# Test_Jig_PPM-Encoder.net
KiCad netlist of a schematic drawn in Altium Designer
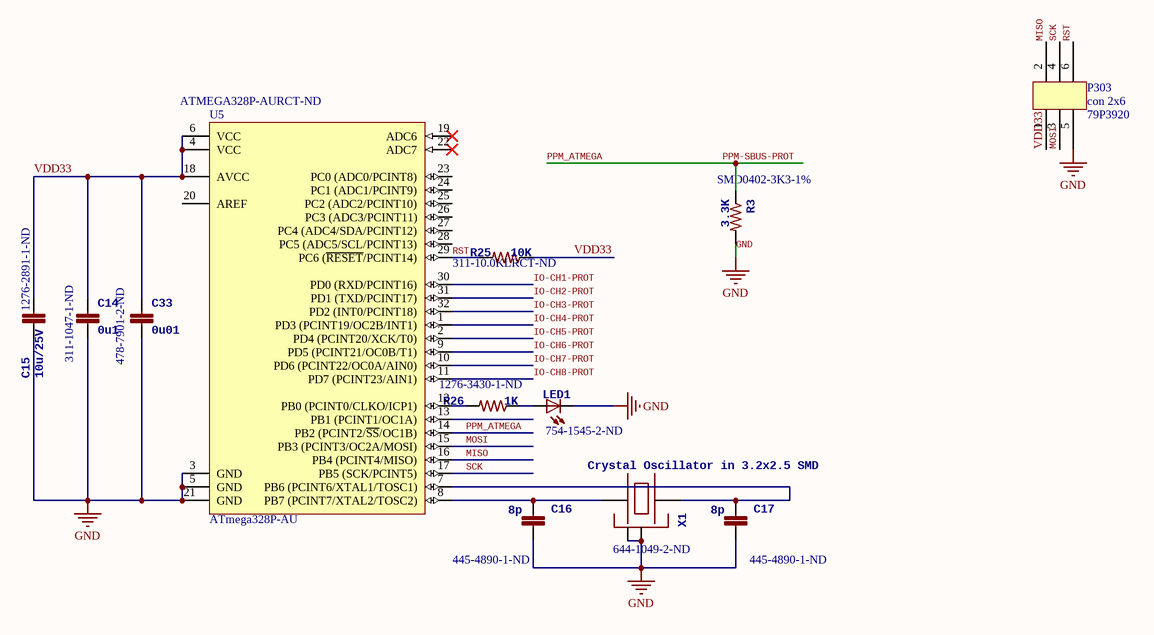
[diagram p0: Test_Jig_PPM-Encoder.SchDoc]

(export (version "E")
  (design (tool "Eeschema 10.0.6"))
  (components
    (comp (ref "C14")
      (value "0u1")
      (footprint "0402-CAP")
      (description "CAP CER 0.1UF 16V Y5V 0402")
      (fields
        (field (name "PARTNO") "CC0402ZRY5V7BB104")
        (field (name "SUPPLIER PART NUMBER 1") "311-1047-1-ND")
        (field (name "3DR_PARTNO") "ECM0700")
      )
      (libsource (lib "pixhawk2") (part "CAP0402"))
    )
    (comp (ref "C15")
      (value "10u/25V")
      (footprint "0805-CAP")
      (description "CAP CER 10UF 25V 10% X5R 0805")
      (fields
        (field (name "PARTNO") "CL21A106KAYNNNE")
        (field (name "SUPPLIER PART NUMBER 1") "1276-2891-1-ND")
        (field (name "3DR_PARTNO") "ECM0714")
      )
      (libsource (lib "pixhawk2") (part "CAP0805"))
    )
    (comp (ref "C16")
      (value "8p")
      (footprint "0402-CAP")
      (description "CAP CER 8PF 50V C0G 0402")
      (fields
        (field (name "PARTNO") "C1005C0G1H080C")
        (field (name "SUPPLIER PART NUMBER 1") "445-4890-1-ND")
        (field (name "3DR_PARTNO") "ECM0710")
      )
      (libsource (lib "") (part "CAP0402_1"))
    )
    (comp (ref "C17")
      (value "8p")
      (footprint "0402-CAP")
      (description "CAP CER 8PF 50V C0G 0402")
      (fields
        (field (name "PARTNO") "C1005C0G1H080C")
        (field (name "SUPPLIER PART NUMBER 1") "445-4890-1-ND")
        (field (name "3DR_PARTNO") "ECM0710")
      )
      (libsource (lib "") (part "CAP0402_1"))
    )
    (comp (ref "C33")
      (value "0u01")
      (footprint "0603-CAP")
      (description "CAP CER 10000PF 25V 5% X7R 0603")
      (fields
        (field (name "PARTNO") "06033C103JAT2A")
        (field (name "SUPPLIER PART NUMBER 1") "478-7901-2-ND")
        (field (name "3DR_PARTNO") "ECM0620")
      )
      (libsource (lib "pixhawk2") (part "CAP0603"))
    )
    (comp (ref "LED1")
      (value "LED0603_Green")
      (footprint "0603-LED-Blue")
      (description "LED GREEN ROUND CLEAR SMD")
      (fields
        (field (name "SUPPLIER PART NUMBER 1") "754-1545-2-ND")
        (field (name "3DR_PARTNO") "ECM0494")
        (field (name "PARTNO") "APTD1608CGCK")
      )
      (libsource (lib "pixhawk2") (part "LED0603_Blue"))
    )
    (comp (ref "P303")
      (value "con 2x6")
      (footprint "TSW-103-07-G-D")
      (description "Connector, Header, 6Pos, 2.54MM, Vert, THT, Au")
      (fields (field (name "SUPPLIER PART NUMBER 1") "79P3920") (field (name "3DR_PARTNO") "PRT0445"))
      (libsource (lib "PCA_0005_FULL_CB_REV_A") (part "con 2x6"))
    )
    (comp (ref "R3")
      (value "3.3K")
      (footprint "C0402")
      (fields (field (name "SUPPLIER PART NUMBER 1") "SMD0402-3K3-1%"))
      (libsource (lib "DIYdrones3") (part "RESISTOR0402"))
    )
    (comp (ref "R25")
      (value "10K")
      (footprint "0402-RES")
      (description "RES 10K OHM 1/16W 1% 0402 SMD")
      (fields
        (field (name "PARTNO") "RC0402FR-0710KL")
        (field (name "SUPPLIER PART NUMBER 1") "311-10.0KLRCT-ND")
        (field (name "3DR_PARTNO") "ECM0800")
      )
      (libsource (lib "pixhawk2") (part "RESISTOR0402-RES"))
    )
    (comp (ref "R26")
      (value "1K")
      (footprint "0402-RES")
      (description "RES 1K OHM 1/16W 1% 0402")
      (fields
        (field (name "PARTNO") "RC1005F102CS")
        (field (name "SUPPLIER PART NUMBER 1") "1276-3430-1-ND")
        (field (name "3DR_PARTNO") "ECM0804")
      )
      (libsource (lib "pixhawk2") (part "RESISTOR0402-RES"))
    )
    (comp (ref "U5")
      (value "ATmega328P-AU")
      (footprint "32A_N")
      (fields (field (name "SUPPLIER PART NUMBER 1") "ATMEGA328P-AURCT-ND"))
      (libsource (lib "Atmel Microcontroller megaAVR") (part "ATmega328P-AU"))
    )
    (comp (ref "X1")
      (value "Crystal Oscillator in 3.2x2.5 SMD")
      (footprint "OSCILLATOR-3.2X2.5")
      (description "CRYSTAL 16MHZ 8PF SMD")
      (fields
        (field (name "SUPPLIER PART NUMBER 1") "644-1049-2-ND")
        (field (name "PARTNO") "NX3225SA-16.000MHZ-STD-CSR-1")
      )
      (libsource (lib "pixhawk2") (part "OSCILLATOR-3.2X2.5"))
    )
  )
  (nets
    (net (code "1") (name "/IO-CH1-PROT") (class "Default")
      (node (ref "U5") (pin "30") (pinfunction "PD0_(RXD/PCINT16)_30") (pintype "bidirectional"))
    )
    (net (code "2") (name "/IO-CH2-PROT") (class "Default")
      (node (ref "U5") (pin "31") (pinfunction "PD1_(TXD/PCINT17)_31") (pintype "bidirectional"))
    )
    (net (code "3") (name "/IO-CH3-PROT") (class "Default")
      (node (ref "U5") (pin "32") (pinfunction "PD2_(INT0/PCINT18)_32") (pintype "bidirectional"))
    )
    (net (code "4") (name "/IO-CH4-PROT") (class "Default")
      (node (ref "U5") (pin "1") (pinfunction "PD3_(PCINT19/OC2B/INT1)_1") (pintype "bidirectional"))
    )
    (net (code "5") (name "/IO-CH5-PROT") (class "Default")
      (node (ref "U5") (pin "2") (pinfunction "PD4_(PCINT20/XCK/T0)_2") (pintype "bidirectional"))
    )
    (net (code "6") (name "/IO-CH6-PROT") (class "Default")
      (node (ref "U5") (pin "9") (pinfunction "PD5_(PCINT21/OC0B/T1)_9") (pintype "bidirectional"))
    )
    (net (code "7") (name "/IO-CH7-PROT") (class "Default")
      (node (ref "U5") (pin "10") (pinfunction "PD6_(PCINT22/OC0A/AIN0)_10") (pintype "bidirectional"))
    )
    (net (code "8") (name "/IO-CH8-PROT") (class "Default")
      (node (ref "U5") (pin "11") (pinfunction "PD7_(PCINT23/AIN1)_11") (pintype "bidirectional"))
    )
    (net (code "9") (name "/MISO") (class "Default")
      (node (ref "P303") (pin "2") (pinfunction "2_2") (pintype "passive"))
      (node (ref "U5") (pin "16") (pinfunction "PB4_(PCINT4/MISO)_16") (pintype "bidirectional"))
    )
    (net (code "10") (name "/MOSI") (class "Default")
      (node (ref "P303") (pin "3") (pinfunction "3_3") (pintype "passive"))
      (node (ref "U5") (pin "15") (pinfunction "PB3_(PCINT3/OC2A/MOSI)_15") (pintype "bidirectional"))
    )
    (net (code "11") (name "/PPM-SBUS-PROT") (class "Default")
      (node (ref "R3") (pin "1") (pinfunction "1_1") (pintype "passive"))
      (node (ref "U5") (pin "14") (pinfunction "PB2_(PCINT2/~{SS}/OC1B)_14") (pintype "bidirectional"))
    )
    (net (code "12") (name "/RST") (class "Default")
      (node (ref "P303") (pin "6") (pinfunction "6_6") (pintype "passive"))
      (node (ref "R25") (pin "P$2") (pinfunction "2_P$2") (pintype "passive"))
      (node (ref "U5") (pin "29") (pinfunction "PC6_(~{RESET}/PCINT14)_29") (pintype "bidirectional"))
    )
    (net (code "13") (name "/SCK") (class "Default")
      (node (ref "P303") (pin "4") (pinfunction "4_4") (pintype "passive"))
      (node (ref "U5") (pin "17") (pinfunction "PB5_(SCK/PCINT5)_17") (pintype "bidirectional"))
    )
    (net (code "14") (name "/VDD33") (class "Default")
      (node (ref "C14") (pin "P$1") (pinfunction "1_P$1") (pintype "passive"))
      (node (ref "C15") (pin "P$1") (pinfunction "1_P$1") (pintype "passive"))
      (node (ref "C33") (pin "P$1") (pinfunction "1_P$1") (pintype "passive"))
      (node (ref "P303") (pin "1") (pinfunction "1_1") (pintype "passive"))
      (node (ref "R25") (pin "P$1") (pinfunction "1_P$1") (pintype "passive"))
      (node (ref "U5") (pin "18") (pinfunction "AVCC_18") (pintype "power_in"))
      (node (ref "U5") (pin "4") (pinfunction "VCC_4") (pintype "power_in"))
      (node (ref "U5") (pin "6") (pinfunction "VCC_6") (pintype "power_in"))
    )
    (net (code "15") (name "GND") (class "Default")
      (node (ref "C14") (pin "P$2") (pinfunction "2_P$2") (pintype "passive"))
      (node (ref "C15") (pin "P$2") (pinfunction "2_P$2") (pintype "passive"))
      (node (ref "C16") (pin "P$1") (pinfunction "1_P$1") (pintype "passive"))
      (node (ref "C17") (pin "P$1") (pinfunction "1_P$1") (pintype "passive"))
      (node (ref "C33") (pin "P$2") (pinfunction "2_P$2") (pintype "passive"))
      (node (ref "LED1") (pin "C") (pinfunction "C_C") (pintype "passive"))
      (node (ref "P303") (pin "5") (pinfunction "5_5") (pintype "passive"))
      (node (ref "R3") (pin "2") (pinfunction "2_2") (pintype "passive"))
      (node (ref "U5") (pin "21") (pinfunction "GND_21") (pintype "power_in"))
      (node (ref "U5") (pin "3") (pinfunction "GND_3") (pintype "power_in"))
      (node (ref "U5") (pin "5") (pinfunction "GND_5") (pintype "power_in"))
      (node (ref "X1") (pin "2") (pinfunction "NC_2_2") (pintype "open_emitter"))
      (node (ref "X1") (pin "4") (pinfunction "NC_4_4") (pintype "open_emitter"))
    )
    (net (code "16") (name "Net-(C16-2)") (class "Default")
      (node (ref "C16") (pin "P$2") (pinfunction "2_P$2") (pintype "passive"))
      (node (ref "U5") (pin "8") (pinfunction "PB7_(PCINT7/XTAL2/TOSC2)_8") (pintype "bidirectional"))
      (node (ref "X1") (pin "1") (pinfunction "1_1") (pintype "passive"))
    )
    (net (code "17") (name "Net-(C17-2)") (class "Default")
      (node (ref "C17") (pin "P$2") (pinfunction "2_P$2") (pintype "passive"))
      (node (ref "U5") (pin "7") (pinfunction "PB6_(PCINT6/XTAL1/TOSC1)_7") (pintype "bidirectional"))
      (node (ref "X1") (pin "3") (pinfunction "3_3") (pintype "passive"))
    )
    (net (code "18") (name "Net-(R26-1)") (class "Default")
      (node (ref "LED1") (pin "A") (pinfunction "A_A") (pintype "passive"))
      (node (ref "R26") (pin "P$1") (pinfunction "1_P$1") (pintype "passive"))
    )
    (net (code "19") (name "Net-(R26-2)") (class "Default")
      (node (ref "R26") (pin "P$2") (pinfunction "2_P$2") (pintype "passive"))
      (node (ref "U5") (pin "12") (pinfunction "PB0_(PCINT0/CLKO/ICP1)_12") (pintype "bidirectional"))
    )
    (net (code "20") (name "unconnected-(U5-ADC6-Pad19)") (class "Default")
      (node (ref "U5") (pin "19") (pinfunction "ADC6_19") (pintype "input+no_connect"))
    )
    (net (code "21") (name "unconnected-(U5-ADC7-Pad22)") (class "Default")
      (node (ref "U5") (pin "22") (pinfunction "ADC7_22") (pintype "input+no_connect"))
    )
    (net (code "22") (name "unconnected-(U5-AREF-Pad20)") (class "Default")
      (node (ref "U5") (pin "20") (pinfunction "AREF_20") (pintype "passive"))
    )
    (net (code "23") (name "unconnected-(U5-PB1_(PCINT1{slash}OC1A)-Pad13)") (class "Default")
      (node (ref "U5") (pin "13") (pinfunction "PB1_(PCINT1/OC1A)_13") (pintype "bidirectional"))
    )
    (net (code "24") (name "unconnected-(U5-PC0_(ADC0{slash}PCINT8)-Pad23)") (class "Default")
      (node (ref "U5") (pin "23") (pinfunction "PC0_(ADC0/PCINT8)_23") (pintype "bidirectional"))
    )
    (net (code "25") (name "unconnected-(U5-PC1_(ADC1{slash}PCINT9)-Pad24)") (class "Default")
      (node (ref "U5") (pin "24") (pinfunction "PC1_(ADC1/PCINT9)_24") (pintype "bidirectional"))
    )
    (net (code "26") (name "unconnected-(U5-PC2_(ADC2{slash}PCINT10)-Pad25)") (class "Default")
      (node (ref "U5") (pin "25") (pinfunction "PC2_(ADC2/PCINT10)_25") (pintype "bidirectional"))
    )
    (net (code "27") (name "unconnected-(U5-PC3_(ADC3{slash}PCINT11)-Pad26)") (class "Default")
      (node (ref "U5") (pin "26") (pinfunction "PC3_(ADC3/PCINT11)_26") (pintype "bidirectional"))
    )
    (net (code "28") (name "unconnected-(U5-PC4_(ADC4{slash}SDA{slash}PCINT12)-Pad27)") (class "Default")
      (node (ref "U5") (pin "27") (pinfunction "PC4_(ADC4/SDA/PCINT12)_27") (pintype "bidirectional"))
    )
    (net (code "29") (name "unconnected-(U5-PC5_(ADC5{slash}SCL{slash}PCINT13)-Pad28)") (class "Default")
      (node (ref "U5") (pin "28") (pinfunction "PC5_(ADC5/SCL/PCINT13)_28") (pintype "bidirectional"))
    )
  )
)
